# solenoid_drv.net
KiCad netlist of a schematic drawn in Altium Designer
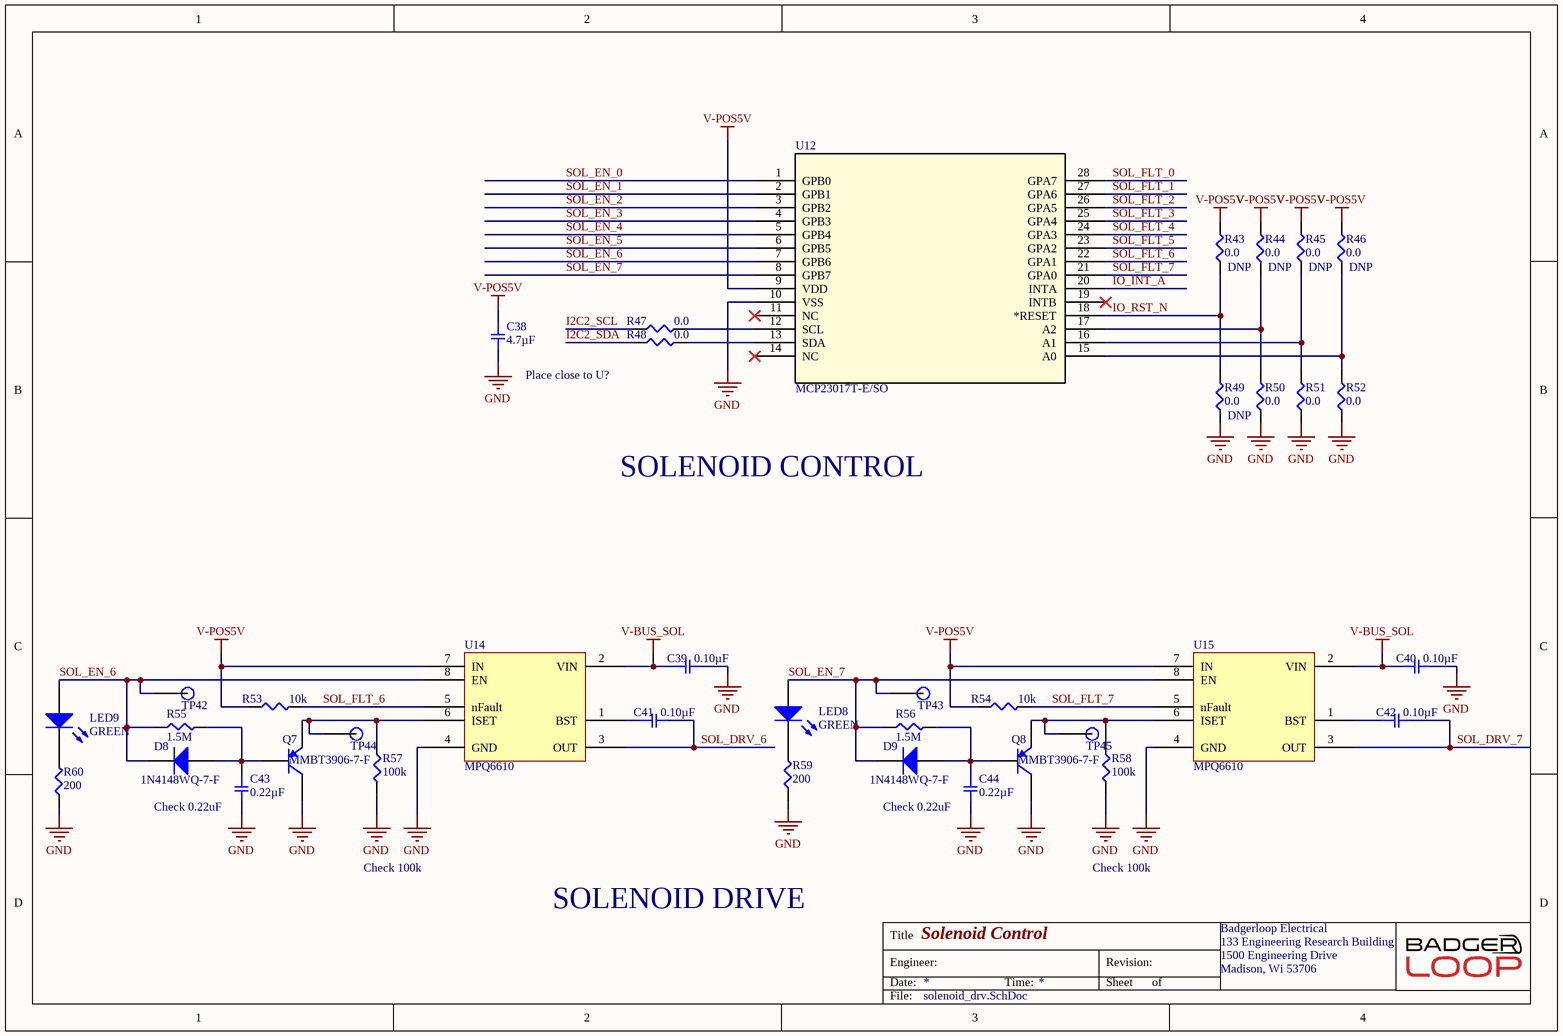
[diagram p0: solenoid_drv.SchDoc]

(export (version "E")
  (design (tool "Eeschema 10.0.6"))
  (components
    (comp (ref "C38")
      (value "4.7µF")
      (footprint "SMD-0805C")
      (description "CAP CER 4.7UF 6.3V X5R 0805")
      (fields
        (field (name "DIGI-KEY PART NUMBER") "490-9749-1-ND")
        (field (name "PART NUMBER") "GRM21BR60J475KA11L")
      )
      (libsource (lib "capacitor") (part "GRM21BR60J475KA11L"))
    )
    (comp (ref "C39")
      (value "0.10µF")
      (footprint "SMD-0805C")
      (description "CAP CER 0.1UF 10V U2J 0805")
      (fields
        (field (name "DIGI-KEY PART NUMBER") "490-11592-1-ND")
        (field (name "PART NUMBER") "GRM21B7U1A104JA01L")
      )
      (libsource (lib "capacitors") (part "GRM21B7U1A104JA01L"))
    )
    (comp (ref "C40")
      (value "0.10µF")
      (footprint "SMD-0805C")
      (description "CAP CER 0.1UF 10V U2J 0805")
      (fields
        (field (name "DIGI-KEY PART NUMBER") "490-11592-1-ND")
        (field (name "PART NUMBER") "GRM21B7U1A104JA01L")
      )
      (libsource (lib "capacitors") (part "GRM21B7U1A104JA01L"))
    )
    (comp (ref "C41")
      (value "0.10µF")
      (footprint "SMD-0805C")
      (description "CAP CER 0.1UF 10V U2J 0805")
      (fields
        (field (name "DIGI-KEY PART NUMBER") "490-11592-1-ND")
        (field (name "PART NUMBER") "GRM21B7U1A104JA01L")
      )
      (libsource (lib "capacitors") (part "GRM21B7U1A104JA01L"))
    )
    (comp (ref "C42")
      (value "0.10µF")
      (footprint "SMD-0805C")
      (description "CAP CER 0.1UF 10V U2J 0805")
      (fields
        (field (name "DIGI-KEY PART NUMBER") "490-11592-1-ND")
        (field (name "PART NUMBER") "GRM21B7U1A104JA01L")
      )
      (libsource (lib "capacitors") (part "GRM21B7U1A104JA01L"))
    )
    (comp (ref "C43")
      (value "0.22µF")
      (footprint "SMD-0805C")
      (description "CAP CER 0.22UF 10V X7R 0805")
      (fields
        (field (name "DIGI-KEY PART NUMBER") "490-4432-1-ND")
        (field (name "PART NUMBER") "LLA215R71A224MA14L")
      )
      (libsource (lib "capacitors") (part "LLA215R71A224MA14L"))
    )
    (comp (ref "C44")
      (value "0.22µF")
      (footprint "SMD-0805C")
      (description "CAP CER 0.22UF 10V X7R 0805")
      (fields
        (field (name "DIGI-KEY PART NUMBER") "490-4432-1-ND")
        (field (name "PART NUMBER") "LLA215R71A224MA14L")
      )
      (libsource (lib "capacitors") (part "LLA215R71A224MA14L"))
    )
    (comp (ref "D8")
      (value "1N4148WQ-7-F")
      (footprint "SODFL350X80-2N")
      (description "Diodes - General Purpose, Power, Switching SMT Fast Switching Diode")
      (fields (field (name "MANUFACTURER") "Diodes Inc."))
      (libsource (lib "misc") (part "1N4148WQ-7-F"))
    )
    (comp (ref "D9")
      (value "1N4148WQ-7-F")
      (footprint "SODFL350X80-2N")
      (description "Diodes - General Purpose, Power, Switching SMT Fast Switching Diode")
      (fields (field (name "MANUFACTURER") "Diodes Inc."))
      (libsource (lib "misc") (part "1N4148WQ-7-F"))
    )
    (comp (ref "LED8")
      (value "GREEN")
      (footprint "LED 0603 GREEN")
      (fields (field (name "MANUFACTURER") "Lite-On Inc."))
      (libsource (lib "misc") (part "LED GREEN 0603"))
    )
    (comp (ref "LED9")
      (value "GREEN")
      (footprint "LED 0603 GREEN")
      (fields (field (name "MANUFACTURER") "Lite-On Inc."))
      (libsource (lib "misc") (part "LED GREEN 0603"))
    )
    (comp (ref "Q7")
      (value "MMBT3906-7-F")
      (footprint "SOTFL103P240X110-3N")
      (fields (field (name "MANUFACTURER") "Diodes Zetex"))
      (libsource (lib "misc") (part "MMBT3906-7-F"))
    )
    (comp (ref "Q8")
      (value "MMBT3906-7-F")
      (footprint "SOTFL103P240X110-3N")
      (fields (field (name "MANUFACTURER") "Diodes Zetex"))
      (libsource (lib "misc") (part "MMBT3906-7-F"))
    )
    (comp (ref "R43")
      (value "0.0")
      (footprint "SMD-0805-RES")
      (description "RES SMD 0.0 OHM JUMPER 1/8W 0805")
      (fields
        (field (name "PART NUMBER") "ERJ-6GEY0R00V")
        (field (name "DIGI-KEY PART NUMBER") "P0.0ACT-ND")
        (field (name "DNP") "DNP")
      )
      (libsource (lib "resistors") (part "ERJ-6GEY0R00V"))
    )
    (comp (ref "R44")
      (value "0.0")
      (footprint "SMD-0805-RES")
      (description "RES SMD 0.0 OHM JUMPER 1/8W 0805")
      (fields
        (field (name "PART NUMBER") "ERJ-6GEY0R00V")
        (field (name "DIGI-KEY PART NUMBER") "P0.0ACT-ND")
        (field (name "DNP") "DNP")
      )
      (libsource (lib "resistors") (part "ERJ-6GEY0R00V"))
    )
    (comp (ref "R45")
      (value "0.0")
      (footprint "SMD-0805-RES")
      (description "RES SMD 0.0 OHM JUMPER 1/8W 0805")
      (fields
        (field (name "PART NUMBER") "ERJ-6GEY0R00V")
        (field (name "DIGI-KEY PART NUMBER") "P0.0ACT-ND")
        (field (name "DNP") "DNP")
      )
      (libsource (lib "resistors") (part "ERJ-6GEY0R00V"))
    )
    (comp (ref "R46")
      (value "0.0")
      (footprint "SMD-0805-RES")
      (description "RES SMD 0.0 OHM JUMPER 1/8W 0805")
      (fields
        (field (name "PART NUMBER") "ERJ-6GEY0R00V")
        (field (name "DIGI-KEY PART NUMBER") "P0.0ACT-ND")
        (field (name "DNP") "DNP")
      )
      (libsource (lib "resistors") (part "ERJ-6GEY0R00V"))
    )
    (comp (ref "R47")
      (value "0.0")
      (footprint "SMD-0805-RES")
      (description "RES SMD 0.0 OHM JUMPER 1/8W 0805")
      (fields (field (name "PART NUMBER") "ERJ-6GEY0R00V") (field (name "DIGI-KEY PART NUMBER") "P0.0ACT-ND"))
      (libsource (lib "resistors") (part "ERJ-6GEY0R00V"))
    )
    (comp (ref "R48")
      (value "0.0")
      (footprint "SMD-0805-RES")
      (description "RES SMD 0.0 OHM JUMPER 1/8W 0805")
      (fields (field (name "PART NUMBER") "ERJ-6GEY0R00V") (field (name "DIGI-KEY PART NUMBER") "P0.0ACT-ND"))
      (libsource (lib "resistors") (part "ERJ-6GEY0R00V"))
    )
    (comp (ref "R49")
      (value "0.0")
      (footprint "SMD-0805-RES")
      (description "RES SMD 0.0 OHM JUMPER 1/8W 0805")
      (fields
        (field (name "PART NUMBER") "ERJ-6GEY0R00V")
        (field (name "DIGI-KEY PART NUMBER") "P0.0ACT-ND")
        (field (name "DNP") "DNP")
      )
      (libsource (lib "resistors") (part "ERJ-6GEY0R00V"))
    )
    (comp (ref "R50")
      (value "0.0")
      (footprint "SMD-0805-RES")
      (description "RES SMD 0.0 OHM JUMPER 1/8W 0805")
      (fields (field (name "PART NUMBER") "ERJ-6GEY0R00V") (field (name "DIGI-KEY PART NUMBER") "P0.0ACT-ND"))
      (libsource (lib "resistors") (part "ERJ-6GEY0R00V"))
    )
    (comp (ref "R51")
      (value "0.0")
      (footprint "SMD-0805-RES")
      (description "RES SMD 0.0 OHM JUMPER 1/8W 0805")
      (fields (field (name "PART NUMBER") "ERJ-6GEY0R00V") (field (name "DIGI-KEY PART NUMBER") "P0.0ACT-ND"))
      (libsource (lib "resistors") (part "ERJ-6GEY0R00V"))
    )
    (comp (ref "R52")
      (value "0.0")
      (footprint "SMD-0805-RES")
      (description "RES SMD 0.0 OHM JUMPER 1/8W 0805")
      (fields (field (name "PART NUMBER") "ERJ-6GEY0R00V") (field (name "DIGI-KEY PART NUMBER") "P0.0ACT-ND"))
      (libsource (lib "resistors") (part "ERJ-6GEY0R00V"))
    )
    (comp (ref "R53")
      (value "10k")
      (footprint "SMD-0805-RES")
      (description "RES SMD 10K OHM 5% 1/2W 0805")
      (fields (field (name "PART NUMBER") "ERJ-P06J103V") (field (name "DIGI-KEY PART NUMBER") "P10KADCT-ND"))
      (libsource (lib "resistors") (part "ERJ-P06J103V"))
    )
    (comp (ref "R54")
      (value "10k")
      (footprint "SMD-0805-RES")
      (description "RES SMD 10K OHM 5% 1/2W 0805")
      (fields (field (name "PART NUMBER") "ERJ-P06J103V") (field (name "DIGI-KEY PART NUMBER") "P10KADCT-ND"))
      (libsource (lib "resistors") (part "ERJ-P06J103V"))
    )
    (comp (ref "R55")
      (value "1.5M")
      (footprint "SMD-0805-RES")
      (description "RES SMD 1.5M OHM 5% 1/8W 0805")
      (fields
        (field (name "PART NUMBER") "ERJ-6GEYJ155V")
        (field (name "DIGI-KEY PART NUMBER") "P1.5MACT-ND")
      )
      (libsource (lib "resistors") (part "ERJ-6GEYJ155V"))
    )
    (comp (ref "R56")
      (value "1.5M")
      (footprint "SMD-0805-RES")
      (description "RES SMD 1.5M OHM 5% 1/8W 0805")
      (fields
        (field (name "PART NUMBER") "ERJ-6GEYJ155V")
        (field (name "DIGI-KEY PART NUMBER") "P1.5MACT-ND")
      )
      (libsource (lib "resistors") (part "ERJ-6GEYJ155V"))
    )
    (comp (ref "R57")
      (value "100k")
      (footprint "SMD-0805-RES")
      (description "RES SMD 100K OHM 5% 1/2W 0805")
      (fields
        (field (name "PART NUMBER") "ERJ-P06J104V")
        (field (name "DIGI-KEY PART NUMBER") "P100KADCT-ND")
      )
      (libsource (lib "resistors") (part "ERJ-P06J104V"))
    )
    (comp (ref "R58")
      (value "100k")
      (footprint "SMD-0805-RES")
      (description "RES SMD 100K OHM 5% 1/2W 0805")
      (fields
        (field (name "PART NUMBER") "ERJ-P06J104V")
        (field (name "DIGI-KEY PART NUMBER") "P100KADCT-ND")
      )
      (libsource (lib "resistors") (part "ERJ-P06J104V"))
    )
    (comp (ref "R59")
      (value "200")
      (footprint "SMD-0805-RES")
      (description "RES SMD 200 OHM 1% 1/2W 0805")
      (fields
        (field (name "PART NUMBER") "ERJ-P06F2000V")
        (field (name "DIGI-KEY PART NUMBER") "P16064CT-ND")
      )
      (libsource (lib "resistors") (part "ERJ-P06F2000V"))
    )
    (comp (ref "R60")
      (value "200")
      (footprint "SMD-0805-RES")
      (description "RES SMD 200 OHM 1% 1/2W 0805")
      (fields
        (field (name "PART NUMBER") "ERJ-P06F2000V")
        (field (name "DIGI-KEY PART NUMBER") "P16064CT-ND")
      )
      (libsource (lib "resistors") (part "ERJ-P06F2000V"))
    )
    (comp (ref "TP42")
      (value "TP")
      (footprint "Test Point")
      (description "SMD TEST POINT")
      (libsource (lib "misc") (part "TP"))
    )
    (comp (ref "TP43")
      (value "TP")
      (footprint "Test Point")
      (description "SMD TEST POINT")
      (libsource (lib "misc") (part "TP"))
    )
    (comp (ref "TP44")
      (value "TP")
      (footprint "Test Point")
      (description "SMD TEST POINT")
      (libsource (lib "misc") (part "TP"))
    )
    (comp (ref "TP45")
      (value "TP")
      (footprint "Test Point")
      (description "SMD TEST POINT")
      (libsource (lib "misc") (part "TP"))
    )
    (comp (ref "U12")
      (value "MCP23017T-E/SO")
      (footprint "SOIC28-W_MC-M")
      (description "IC I/O EXPANDER I2C 16B 28SOIC")
      (fields (field (name "MANUFACTURER") "Microchip"))
      (libsource (lib "ic") (part "MCP23017T-E/SO"))
    )
    (comp (ref "U14")
      (value "MPQ6610")
      (footprint "SOP127P600X175-8N")
      (libsource (lib "ic") (part "MPQ6610"))
    )
    (comp (ref "U15")
      (value "MPQ6610")
      (footprint "SOP127P600X175-8N")
      (libsource (lib "ic") (part "MPQ6610"))
    )
  )
  (nets
    (net (code "1") (name "/I2C2_SCL") (class "Default")
      (node (ref "R47") (pin "1") (pinfunction "1_1") (pintype "passive"))
    )
    (net (code "2") (name "/I2C2_SDA") (class "Default")
      (node (ref "R48") (pin "1") (pinfunction "1_1") (pintype "passive"))
    )
    (net (code "3") (name "/IO_INT_A") (class "Default")
      (node (ref "U12") (pin "20") (pinfunction "INTA_20") (pintype "passive"))
    )
    (net (code "4") (name "/IO_RST_N") (class "Default")
      (node (ref "R43") (pin "1") (pinfunction "1_1") (pintype "passive"))
      (node (ref "R49") (pin "2") (pinfunction "2_2") (pintype "passive"))
      (node (ref "U12") (pin "18") (pinfunction "*RESET_18") (pintype "passive"))
    )
    (net (code "5") (name "/SOL_DRV_6") (class "Default")
      (node (ref "C41") (pin "2") (pinfunction "2_2") (pintype "passive"))
      (node (ref "U14") (pin "3") (pinfunction "OUT_3") (pintype "passive"))
    )
    (net (code "6") (name "/SOL_DRV_7") (class "Default")
      (node (ref "C42") (pin "2") (pinfunction "2_2") (pintype "passive"))
      (node (ref "U15") (pin "3") (pinfunction "OUT_3") (pintype "passive"))
    )
    (net (code "7") (name "/SOL_EN_0") (class "Default")
      (node (ref "U12") (pin "1") (pinfunction "GPB0_1") (pintype "passive"))
    )
    (net (code "8") (name "/SOL_EN_1") (class "Default")
      (node (ref "U12") (pin "2") (pinfunction "GPB1_2") (pintype "passive"))
    )
    (net (code "9") (name "/SOL_EN_2") (class "Default")
      (node (ref "U12") (pin "3") (pinfunction "GPB2_3") (pintype "passive"))
    )
    (net (code "10") (name "/SOL_EN_3") (class "Default")
      (node (ref "U12") (pin "4") (pinfunction "GPB3_4") (pintype "passive"))
    )
    (net (code "11") (name "/SOL_EN_4") (class "Default")
      (node (ref "U12") (pin "5") (pinfunction "GPB4_5") (pintype "passive"))
    )
    (net (code "12") (name "/SOL_EN_5") (class "Default")
      (node (ref "U12") (pin "6") (pinfunction "GPB5_6") (pintype "passive"))
    )
    (net (code "13") (name "/SOL_EN_6") (class "Default")
      (node (ref "D8") (pin "2") (pinfunction "K_2") (pintype "passive"))
      (node (ref "LED9") (pin "1") (pinfunction "A_1") (pintype "passive"))
      (node (ref "R55") (pin "1") (pinfunction "1_1") (pintype "passive"))
      (node (ref "TP42") (pin "1") (pinfunction "1_1") (pintype "passive"))
      (node (ref "U12") (pin "7") (pinfunction "GPB6_7") (pintype "passive"))
      (node (ref "U14") (pin "8") (pinfunction "EN_8") (pintype "power_in"))
    )
    (net (code "14") (name "/SOL_EN_7") (class "Default")
      (node (ref "D9") (pin "2") (pinfunction "K_2") (pintype "passive"))
      (node (ref "LED8") (pin "1") (pinfunction "A_1") (pintype "passive"))
      (node (ref "R56") (pin "1") (pinfunction "1_1") (pintype "passive"))
      (node (ref "TP43") (pin "1") (pinfunction "1_1") (pintype "passive"))
      (node (ref "U12") (pin "8") (pinfunction "GPB7_8") (pintype "passive"))
      (node (ref "U15") (pin "8") (pinfunction "EN_8") (pintype "power_in"))
    )
    (net (code "15") (name "/SOL_FLT_0") (class "Default")
      (node (ref "U12") (pin "28") (pinfunction "GPA7_28") (pintype "passive"))
    )
    (net (code "16") (name "/SOL_FLT_1") (class "Default")
      (node (ref "U12") (pin "27") (pinfunction "GPA6_27") (pintype "passive"))
    )
    (net (code "17") (name "/SOL_FLT_2") (class "Default")
      (node (ref "U12") (pin "26") (pinfunction "GPA5_26") (pintype "passive"))
    )
    (net (code "18") (name "/SOL_FLT_3") (class "Default")
      (node (ref "U12") (pin "25") (pinfunction "GPA4_25") (pintype "passive"))
    )
    (net (code "19") (name "/SOL_FLT_4") (class "Default")
      (node (ref "U12") (pin "24") (pinfunction "GPA3_24") (pintype "passive"))
    )
    (net (code "20") (name "/SOL_FLT_5") (class "Default")
      (node (ref "U12") (pin "23") (pinfunction "GPA2_23") (pintype "passive"))
    )
    (net (code "21") (name "/SOL_FLT_6") (class "Default")
      (node (ref "R53") (pin "2") (pinfunction "2_2") (pintype "passive"))
      (node (ref "U12") (pin "22") (pinfunction "GPA1_22") (pintype "passive"))
      (node (ref "U14") (pin "5") (pinfunction "nFault_5") (pintype "passive"))
    )
    (net (code "22") (name "/SOL_FLT_7") (class "Default")
      (node (ref "R54") (pin "2") (pinfunction "2_2") (pintype "passive"))
      (node (ref "U12") (pin "21") (pinfunction "GPA0_21") (pintype "passive"))
      (node (ref "U15") (pin "5") (pinfunction "nFault_5") (pintype "passive"))
    )
    (net (code "23") (name "GND") (class "Default")
      (node (ref "C38") (pin "2") (pinfunction "2_2") (pintype "passive"))
      (node (ref "C39") (pin "2") (pinfunction "2_2") (pintype "passive"))
      (node (ref "C40") (pin "2") (pinfunction "2_2") (pintype "passive"))
      (node (ref "C43") (pin "2") (pinfunction "2_2") (pintype "passive"))
      (node (ref "C44") (pin "2") (pinfunction "2_2") (pintype "passive"))
      (node (ref "Q7") (pin "3") (pinfunction "C_3") (pintype "passive"))
      (node (ref "Q8") (pin "3") (pinfunction "C_3") (pintype "passive"))
      (node (ref "R49") (pin "1") (pinfunction "1_1") (pintype "passive"))
      (node (ref "R50") (pin "1") (pinfunction "1_1") (pintype "passive"))
      (node (ref "R51") (pin "1") (pinfunction "1_1") (pintype "passive"))
      (node (ref "R52") (pin "1") (pinfunction "1_1") (pintype "passive"))
      (node (ref "R57") (pin "2") (pinfunction "2_2") (pintype "passive"))
      (node (ref "R58") (pin "2") (pinfunction "2_2") (pintype "passive"))
      (node (ref "R59") (pin "1") (pinfunction "1_1") (pintype "passive"))
      (node (ref "R60") (pin "1") (pinfunction "1_1") (pintype "passive"))
      (node (ref "U12") (pin "10") (pinfunction "VSS_10") (pintype "passive"))
      (node (ref "U14") (pin "4") (pinfunction "GND_4") (pintype "passive"))
      (node (ref "U15") (pin "4") (pinfunction "GND_4") (pintype "passive"))
    )
    (net (code "24") (name "Net-(D8-A)") (class "Default")
      (node (ref "C43") (pin "1") (pinfunction "1_1") (pintype "passive"))
      (node (ref "D8") (pin "1") (pinfunction "A_1") (pintype "passive"))
      (node (ref "Q7") (pin "1") (pinfunction "B_1") (pintype "passive"))
      (node (ref "R55") (pin "2") (pinfunction "2_2") (pintype "passive"))
    )
    (net (code "25") (name "Net-(D9-A)") (class "Default")
      (node (ref "C44") (pin "1") (pinfunction "1_1") (pintype "passive"))
      (node (ref "D9") (pin "1") (pinfunction "A_1") (pintype "passive"))
      (node (ref "Q8") (pin "1") (pinfunction "B_1") (pintype "passive"))
      (node (ref "R56") (pin "2") (pinfunction "2_2") (pintype "passive"))
    )
    (net (code "26") (name "Net-(LED8-K)") (class "Default")
      (node (ref "LED8") (pin "2") (pinfunction "K_2") (pintype "passive"))
      (node (ref "R59") (pin "2") (pinfunction "2_2") (pintype "passive"))
    )
    (net (code "27") (name "Net-(LED9-K)") (class "Default")
      (node (ref "LED9") (pin "2") (pinfunction "K_2") (pintype "passive"))
      (node (ref "R60") (pin "2") (pinfunction "2_2") (pintype "passive"))
    )
    (net (code "28") (name "Net-(Q7-E)") (class "Default")
      (node (ref "Q7") (pin "2") (pinfunction "E_2") (pintype "passive"))
      (node (ref "R57") (pin "1") (pinfunction "1_1") (pintype "passive"))
      (node (ref "TP44") (pin "1") (pinfunction "1_1") (pintype "passive"))
      (node (ref "U14") (pin "6") (pinfunction "ISET_6") (pintype "power_in"))
    )
    (net (code "29") (name "Net-(Q8-E)") (class "Default")
      (node (ref "Q8") (pin "2") (pinfunction "E_2") (pintype "passive"))
      (node (ref "R58") (pin "1") (pinfunction "1_1") (pintype "passive"))
      (node (ref "TP45") (pin "1") (pinfunction "1_1") (pintype "passive"))
      (node (ref "U15") (pin "6") (pinfunction "ISET_6") (pintype "power_in"))
    )
    (net (code "30") (name "Net-(U12-A0)") (class "Default")
      (node (ref "R46") (pin "1") (pinfunction "1_1") (pintype "passive"))
      (node (ref "R52") (pin "2") (pinfunction "2_2") (pintype "passive"))
      (node (ref "U12") (pin "15") (pinfunction "A0_15") (pintype "passive"))
    )
    (net (code "31") (name "Net-(U12-A1)") (class "Default")
      (node (ref "R45") (pin "1") (pinfunction "1_1") (pintype "passive"))
      (node (ref "R51") (pin "2") (pinfunction "2_2") (pintype "passive"))
      (node (ref "U12") (pin "16") (pinfunction "A1_16") (pintype "passive"))
    )
    (net (code "32") (name "Net-(U12-A2)") (class "Default")
      (node (ref "R44") (pin "1") (pinfunction "1_1") (pintype "passive"))
      (node (ref "R50") (pin "2") (pinfunction "2_2") (pintype "passive"))
      (node (ref "U12") (pin "17") (pinfunction "A2_17") (pintype "passive"))
    )
    (net (code "33") (name "Net-(U12-SCL)") (class "Default")
      (node (ref "R47") (pin "2") (pinfunction "2_2") (pintype "passive"))
      (node (ref "U12") (pin "12") (pinfunction "SCL_12") (pintype "passive"))
    )
    (net (code "34") (name "Net-(U12-SDA)") (class "Default")
      (node (ref "R48") (pin "2") (pinfunction "2_2") (pintype "passive"))
      (node (ref "U12") (pin "13") (pinfunction "SDA_13") (pintype "passive"))
    )
    (net (code "35") (name "Net-(U14-BST)") (class "Default")
      (node (ref "C41") (pin "1") (pinfunction "1_1") (pintype "passive"))
      (node (ref "U14") (pin "1") (pinfunction "BST_1") (pintype "passive"))
    )
    (net (code "36") (name "Net-(U15-BST)") (class "Default")
      (node (ref "C42") (pin "1") (pinfunction "1_1") (pintype "passive"))
      (node (ref "U15") (pin "1") (pinfunction "BST_1") (pintype "passive"))
    )
    (net (code "37") (name "V-BUS_SOL") (class "Default")
      (node (ref "C39") (pin "1") (pinfunction "1_1") (pintype "passive"))
      (node (ref "C40") (pin "1") (pinfunction "1_1") (pintype "passive"))
      (node (ref "U14") (pin "2") (pinfunction "VIN_2") (pintype "passive"))
      (node (ref "U15") (pin "2") (pinfunction "VIN_2") (pintype "passive"))
    )
    (net (code "38") (name "V-POS5V") (class "Default")
      (node (ref "C38") (pin "1") (pinfunction "1_1") (pintype "passive"))
      (node (ref "R43") (pin "2") (pinfunction "2_2") (pintype "passive"))
      (node (ref "R44") (pin "2") (pinfunction "2_2") (pintype "passive"))
      (node (ref "R45") (pin "2") (pinfunction "2_2") (pintype "passive"))
      (node (ref "R46") (pin "2") (pinfunction "2_2") (pintype "passive"))
      (node (ref "R53") (pin "1") (pinfunction "1_1") (pintype "passive"))
      (node (ref "R54") (pin "1") (pinfunction "1_1") (pintype "passive"))
      (node (ref "U12") (pin "9") (pinfunction "VDD_9") (pintype "passive"))
      (node (ref "U14") (pin "7") (pinfunction "IN_7") (pintype "passive"))
      (node (ref "U15") (pin "7") (pinfunction "IN_7") (pintype "passive"))
    )
    (net (code "39") (name "unconnected-(U12-INTB-Pad19)") (class "Default")
      (node (ref "U12") (pin "19") (pinfunction "INTB_19") (pintype "passive+no_connect"))
    )
    (net (code "40") (name "unconnected-(U12-NC-Pad11)") (class "Default")
      (node (ref "U12") (pin "11") (pinfunction "NC_11") (pintype "passive+no_connect"))
    )
    (net (code "41") (name "unconnected-(U12-NC-Pad14)") (class "Default")
      (node (ref "U12") (pin "14") (pinfunction "NC_14") (pintype "passive+no_connect"))
    )
  )
)
